# DC-DC_10V5.net
KiCad netlist of a schematic drawn in Altium Designer
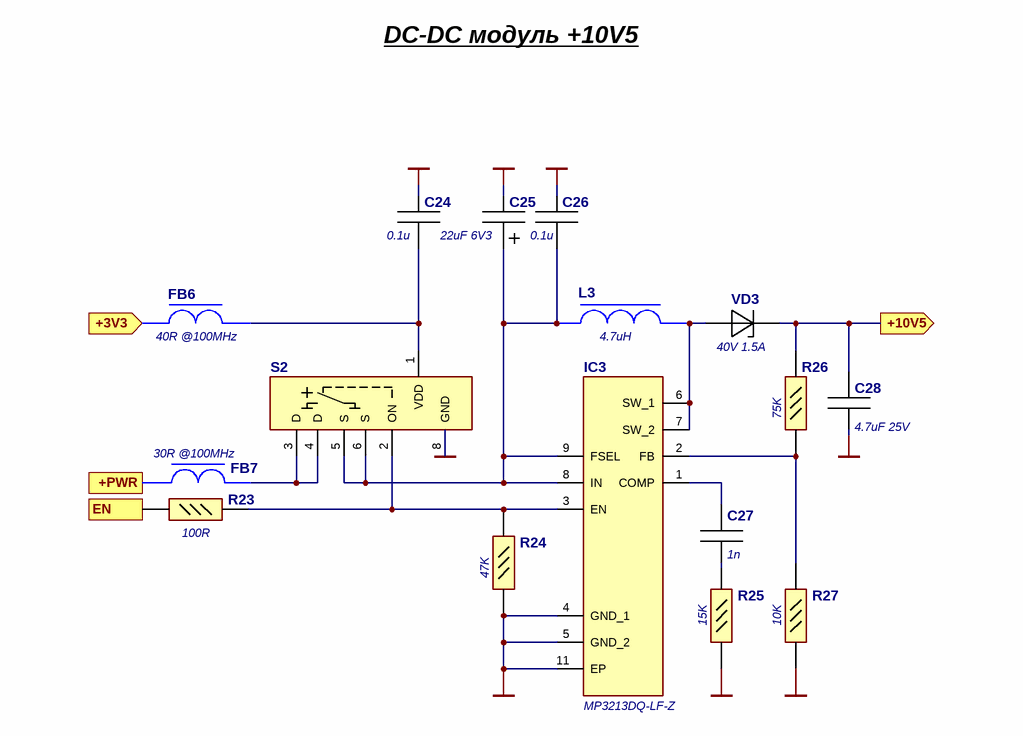
[diagram p0: DC-DC модуль +10V5.SchDoc]

(export (version "E")
  (design (tool "Eeschema 10.0.6"))
  (components
    (comp (ref "C24")
      (value "0.1u")
      (footprint ":CAP0402 100x50x50")
      (description "±10% 25V Ceramic Capacitor X7R 0402 (1005 Metric)")
      (fields
        (field (name "MANUFACTURER_PART_NUMBER") "GRM155R71E104KE14J")
        (field (name "MOUSER PART NUMBER") "81-GRM155R71E104KE4J")
      )
      (libsource (lib "Capacitors 0402") (part "GRM155R71E104KE14J"))
    )
    (comp (ref "C25")
      (value "22uF 6V3")
      (footprint ":CAP1206 C3216-18")
      (description "22uF Molded Tantalum Capacitors 6.3V 1206 (3216 Metric) 300mOhm @ 100kHz")
      (fields (field (name "MANUFACTURER_PART_NUMBER") "TPSA226K006R0300"))
      (libsource (lib "Capacitors 1206") (part "TPSA226K006R0300"))
    )
    (comp (ref "C26")
      (value "0.1u")
      (footprint ":CAP0402 100x50x50")
      (description "±10% 25V Ceramic Capacitor X7R 0402 (1005 Metric)")
      (fields
        (field (name "MANUFACTURER_PART_NUMBER") "GRM155R71E104KE14J")
        (field (name "MOUSER PART NUMBER") "81-GRM155R71E104KE4J")
      )
      (libsource (lib "Capacitors 0402") (part "GRM155R71E104KE14J"))
    )
    (comp (ref "C27")
      (value "1n")
      (footprint ":CAP0402 100x50x50")
      (description "±5% 50V Ceramic Capacitor C0G, NP0 0402 (1005 Metric)")
      (fields (field (name "MANUFACTURER_PART_NUMBER") "GRM1555C1H102JA01J"))
      (libsource (lib "Capacitors 0402") (part "GRM1555C1H102JA01J"))
    )
    (comp (ref "C28")
      (value "4.7uF 25V")
      (footprint ":CAP0805 C2012X125")
      (description "CAP CER 4.7uF 25V X7R 0805")
      (fields (field (name "MANUFACTURER_PART_NUMBER") "GRM21BZ71E475KE15L"))
      (libsource (lib "Capacitors 0805") (part "GRM21BZ71E475KE15L"))
    )
    (comp (ref "FB6")
      (value "40R @100MHz")
      (footprint ":FER MMZ1005Y400CTD25")
      (description "40 Ohms @ 100MHz 1 Signal Line Ferrite Bead 0402 (1005 Metric) 550mA 100mOhm")
      (fields
        (field (name "MANUFACTURER_PART_NUMBER") "MMZ1005Y400CTD25")
        (field (name "MOUSER PART NUMBER") "810-MMZ1005Y400CTD25")
      )
      (libsource (lib "Ferrite Bead") (part "MMZ1005Y400CTD25"))
    )
    (comp (ref "FB7")
      (value "30R @100MHz")
      (footprint ":FER BLM18SP300SN1D")
      (description "30 Ohms @ 100MHz 1 Power Line Ferrite Bead 0603 (1608 Metric) 6A 8mOhm")
      (fields
        (field (name "MANUFACTURER_PART_NUMBER") "BLM18SP300SN1D")
        (field (name "MOUSER PART NUMBER") "81-BLM18SP300SN1D")
      )
      (libsource (lib "Ferrite Bead") (part "BLM18SP300SN1D"))
    )
    (comp (ref "IC3")
      (value "MP3213DQ-LF-Z")
      (footprint ":QFN10 P300X300X100-11N-D")
      (description "DC/DC Converter \r\n3...22V 3.5A")
      (fields (field (name "MOUSER PART NUMBER") "946-MP3213DQLFZ"))
      (libsource (lib "DC-DC convertors") (part "MP3213DQ-LF-Z"))
    )
    (comp (ref "L3")
      (value "4.7uH")
      (footprint ":IND1210 C3225")
      (fields (field (name "MANUFACTURER_PART_NUMBER") "CBC3225T4R7MR"))
      (libsource (lib "Inductance") (part "CBC3225T4R7MR"))
    )
    (comp (ref "R23")
      (value "RC0402FR-07")
      (footprint ":RES0402")
      (fields (field (name "MANUFACTURER_PART_NUMBER (PART 2: VALUE)") "100R"))
      (libsource (lib "") (part "RC0402FR-07_1"))
    )
    (comp (ref "R24")
      (value "RC0402FR-07")
      (footprint ":RES0402")
      (fields (field (name "MANUFACTURER_PART_NUMBER (PART 2: VALUE)") "47K"))
      (libsource (lib "Resistors 0402") (part "RC0402FR-07"))
    )
    (comp (ref "R25")
      (value "RC0402FR-07")
      (footprint ":RES0402")
      (fields (field (name "MANUFACTURER_PART_NUMBER (PART 2: VALUE)") "15K"))
      (libsource (lib "Resistors 0402") (part "RC0402FR-07"))
    )
    (comp (ref "R26")
      (value "RC0402FR-07")
      (footprint ":RES0402")
      (fields (field (name "MANUFACTURER_PART_NUMBER (PART 2: VALUE)") "75K"))
      (libsource (lib "Resistors 0402") (part "RC0402FR-07"))
    )
    (comp (ref "R27")
      (value "RC0402FR-07")
      (footprint ":RES0402")
      (fields (field (name "MANUFACTURER_PART_NUMBER (PART 2: VALUE)") "10K"))
      (libsource (lib "Resistors 0402") (part "RC0402FR-07"))
    )
    (comp (ref "S2")
      (value "4A 7.8mOhm")
      (footprint ":TRAN SLG59M309V")
      (description "Power Switch/Driver 1:1 N-Channel 4A  7.8mOhm 8-FC-TDFN (1.5x2)")
      (fields (field (name "MANUFACTURER_PART_NUMBER") "SLG59M309V"))
      (libsource (lib "Switching and Relays") (part "SLG59M309V"))
    )
    (comp (ref "VD3")
      (value "40V 1.5A")
      (footprint ":DIODE CST2C")
      (description "Diode Schottky 40V 1.5A\r\n@If 550mV @ 1.5A\r\n@Vr 200µA @ 40V")
      (fields (field (name "MANUFACTURER_PART_NUMBER") "CCS15S40,L3F"))
      (libsource (lib "Diodes 0603") (part "CCS15S40,L3F"))
    )
  )
  (nets
    (net (code "1") (name "/+3V3") (class "Default")
      (node (ref "FB6") (pin "2") (pinfunction "2_2") (pintype "passive"))
    )
    (net (code "2") (name "/+10V5") (class "Default")
      (node (ref "C28") (pin "2") (pinfunction "2_2") (pintype "passive"))
      (node (ref "R26") (pin "2") (pinfunction "2_2") (pintype "passive"))
      (node (ref "VD3") (pin "1") (pinfunction "K_1") (pintype "passive"))
    )
    (net (code "3") (name "/+PWR") (class "Default")
      (node (ref "FB7") (pin "1") (pinfunction "1_1") (pintype "passive"))
    )
    (net (code "4") (name "/EN") (class "Default")
      (node (ref "R23") (pin "1") (pinfunction "1_1") (pintype "passive"))
    )
    (net (code "5") (name "GND") (class "Default")
      (node (ref "C24") (pin "1") (pinfunction "1_1") (pintype "passive"))
      (node (ref "C25") (pin "2") (pinfunction "2_2") (pintype "passive"))
      (node (ref "C26") (pin "1") (pinfunction "1_1") (pintype "passive"))
      (node (ref "C28") (pin "1") (pinfunction "1_1") (pintype "passive"))
      (node (ref "IC3") (pin "11") (pinfunction "EP_11") (pintype "passive"))
      (node (ref "IC3") (pin "4") (pinfunction "GND_1_4") (pintype "passive"))
      (node (ref "IC3") (pin "5") (pinfunction "GND_2_5") (pintype "passive"))
      (node (ref "R24") (pin "1") (pinfunction "1_1") (pintype "passive"))
      (node (ref "R25") (pin "1") (pinfunction "1_1") (pintype "passive"))
      (node (ref "R27") (pin "1") (pinfunction "1_1") (pintype "passive"))
      (node (ref "S2") (pin "8") (pinfunction "GND_8") (pintype "passive"))
    )
    (net (code "6") (name "Net-(C25-+)") (class "Default")
      (node (ref "C25") (pin "1") (pinfunction "+_1") (pintype "passive"))
      (node (ref "C26") (pin "2") (pinfunction "2_2") (pintype "passive"))
      (node (ref "IC3") (pin "8") (pinfunction "IN_8") (pintype "passive"))
      (node (ref "IC3") (pin "9") (pinfunction "FSEL_9") (pintype "passive"))
      (node (ref "L3") (pin "1") (pinfunction "1_1") (pintype "passive"))
      (node (ref "S2") (pin "5") (pinfunction "S_5") (pintype "passive"))
      (node (ref "S2") (pin "6") (pinfunction "S_6") (pintype "passive"))
    )
    (net (code "7") (name "Net-(C27-Pad1)") (class "Default")
      (node (ref "C27") (pin "1") (pinfunction "1_1") (pintype "passive"))
      (node (ref "R25") (pin "2") (pinfunction "2_2") (pintype "passive"))
    )
    (net (code "8") (name "Net-(FB7-Pad2)") (class "Default")
      (node (ref "FB7") (pin "2") (pinfunction "2_2") (pintype "passive"))
      (node (ref "S2") (pin "3") (pinfunction "D_3") (pintype "passive"))
      (node (ref "S2") (pin "4") (pinfunction "D_4") (pintype "passive"))
    )
    (net (code "9") (name "Net-(IC3-COMP)") (class "Default")
      (node (ref "C27") (pin "2") (pinfunction "2_2") (pintype "passive"))
      (node (ref "IC3") (pin "1") (pinfunction "COMP_1") (pintype "passive"))
    )
    (net (code "10") (name "Net-(IC3-EN)") (class "Default")
      (node (ref "IC3") (pin "3") (pinfunction "EN_3") (pintype "passive"))
      (node (ref "R23") (pin "2") (pinfunction "2_2") (pintype "passive"))
      (node (ref "R24") (pin "2") (pinfunction "2_2") (pintype "passive"))
      (node (ref "S2") (pin "2") (pinfunction "ON_2") (pintype "passive"))
    )
    (net (code "11") (name "Net-(IC3-FB)") (class "Default")
      (node (ref "IC3") (pin "2") (pinfunction "FB_2") (pintype "passive"))
      (node (ref "R26") (pin "1") (pinfunction "1_1") (pintype "passive"))
      (node (ref "R27") (pin "2") (pinfunction "2_2") (pintype "passive"))
    )
    (net (code "12") (name "Net-(IC3-SW_1)") (class "Default")
      (node (ref "IC3") (pin "6") (pinfunction "SW_1_6") (pintype "passive"))
      (node (ref "IC3") (pin "7") (pinfunction "SW_2_7") (pintype "passive"))
      (node (ref "L3") (pin "2") (pinfunction "2_2") (pintype "passive"))
      (node (ref "VD3") (pin "2") (pinfunction "A_2") (pintype "passive"))
    )
    (net (code "13") (name "Net-(S2-VDD)") (class "Default")
      (node (ref "C24") (pin "2") (pinfunction "2_2") (pintype "passive"))
      (node (ref "FB6") (pin "1") (pinfunction "1_1") (pintype "passive"))
      (node (ref "S2") (pin "1") (pinfunction "VDD_1") (pintype "passive"))
    )
  )
)
